# USB-TTL.net
KiCad netlist of a schematic drawn in EasyEDA Pro
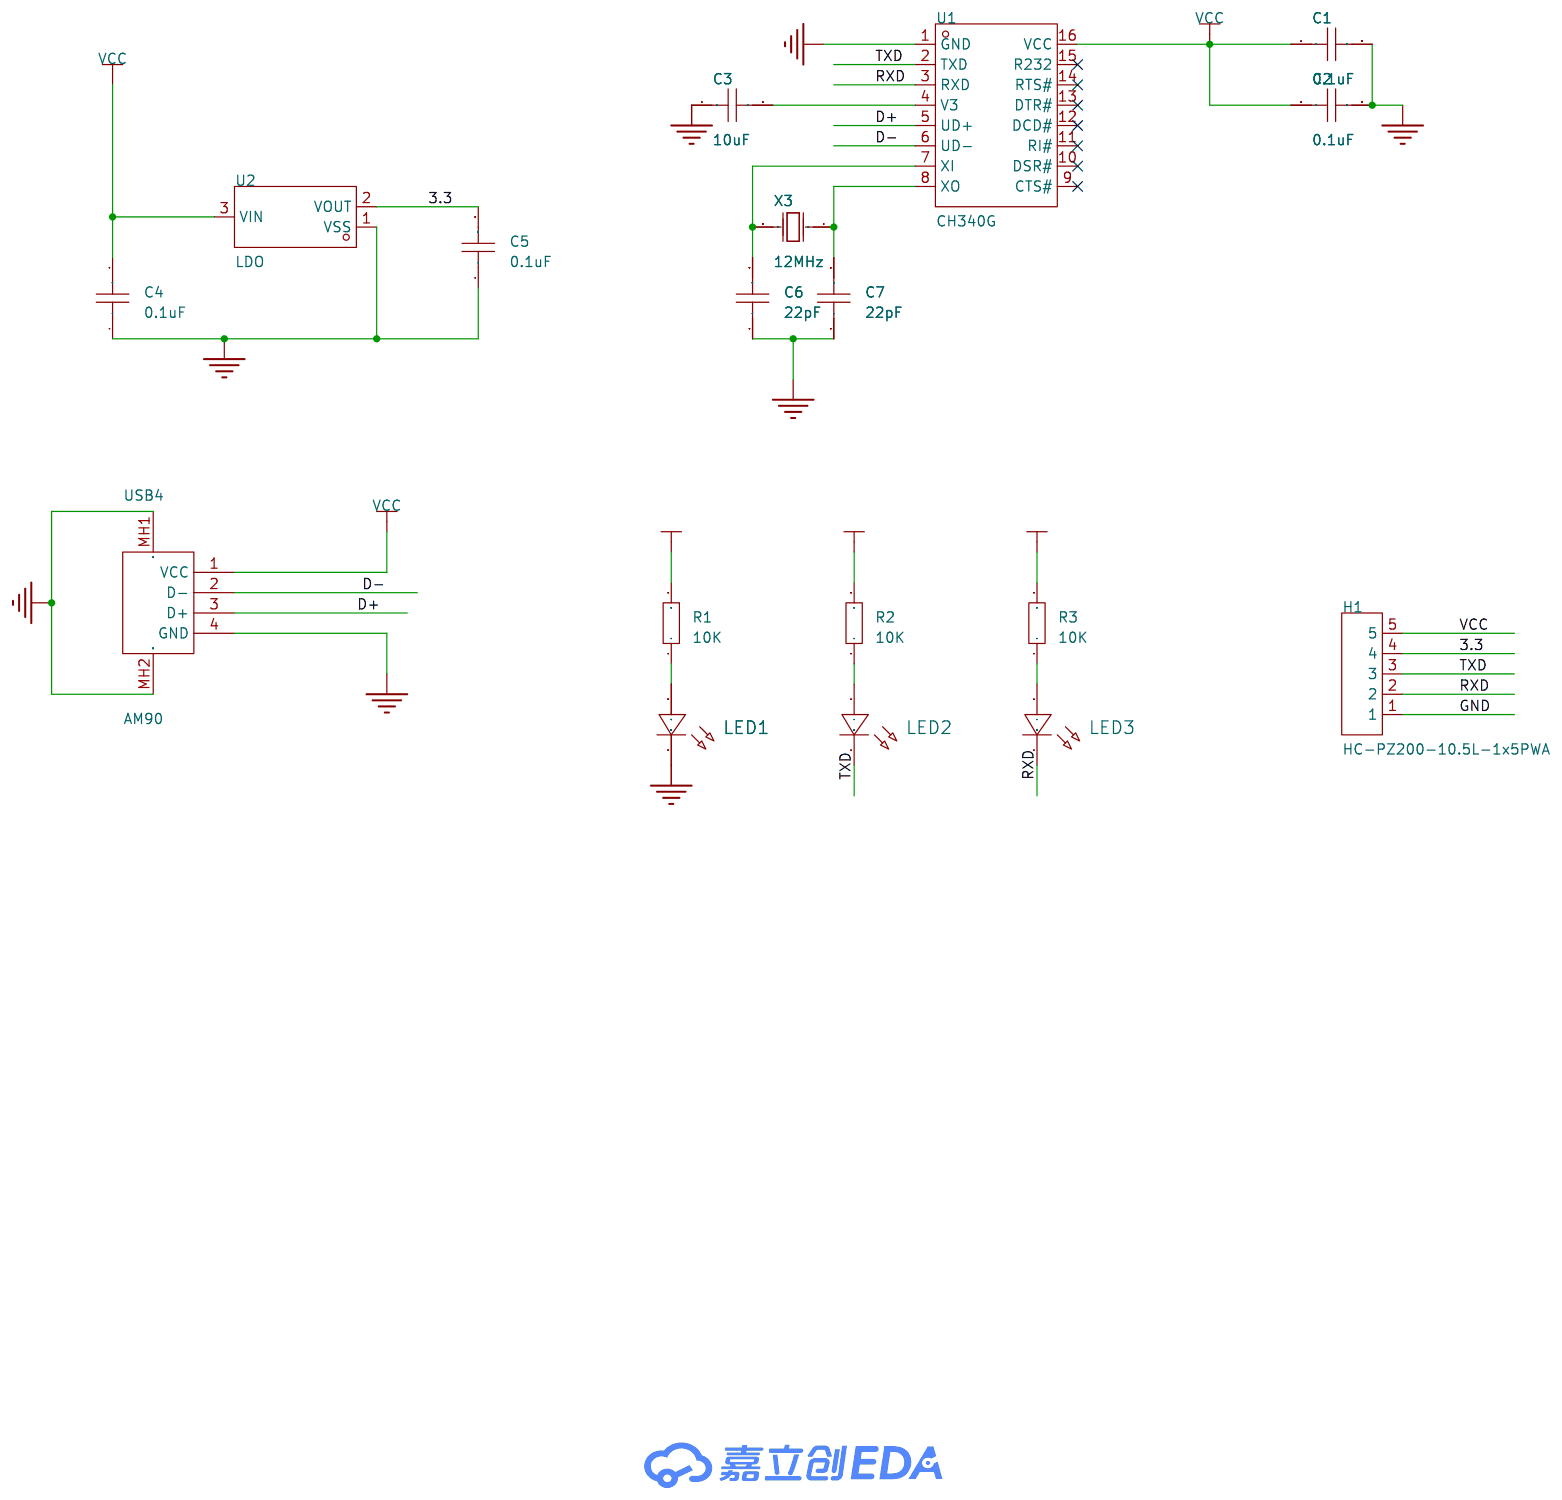
[diagram p0: schematic sheet]

(export (version "E")
  (design (tool "Eeschema 10.0.6"))
  (components
    (comp (ref "C1")
      (value "0.1uF")
      (footprint "easyedapro:C0603")
      (libsource (lib "easyedapro") (part "Capacitance"))
    )
    (comp (ref "C2")
      (value "0.1uF")
      (footprint "easyedapro:C0603")
      (libsource (lib "easyedapro") (part "Capacitance"))
    )
    (comp (ref "C3")
      (value "10uF")
      (footprint "easyedapro:C0603")
      (libsource (lib "easyedapro") (part "Capacitance"))
    )
    (comp (ref "C4")
      (value "0.1uF")
      (footprint "easyedapro:C0603")
      (libsource (lib "easyedapro") (part "Capacitance"))
    )
    (comp (ref "C5")
      (value "0.1uF")
      (footprint "easyedapro:C0603")
      (libsource (lib "easyedapro") (part "Capacitance"))
    )
    (comp (ref "C6")
      (value "22pF")
      (footprint "easyedapro:C0603")
      (libsource (lib "easyedapro") (part "Capacitance"))
    )
    (comp (ref "C7")
      (value "22pF")
      (footprint "easyedapro:C0603")
      (libsource (lib "easyedapro") (part "Capacitance"))
    )
    (comp (ref "H1")
      (value "HC-PZ200-10.5L-1x5PWA")
      (footprint "easyedapro:HDR-TH_5P-P2.00-H-M_2005WR-5P")
      (fields (field (name "Manufacturer") "HC(虹成电子)"))
      (libsource (lib "easyedapro") (part "HC-PZ200-10.5L-1X5PWA"))
    )
    (comp (ref "LED1")
      (value "~")
      (footprint "easyedapro:LED_0603")
      (libsource (lib "easyedapro") (part "LED_R"))
    )
    (comp (ref "LED2")
      (value "~")
      (footprint "easyedapro:LED_0603")
      (libsource (lib "easyedapro") (part "LED_R"))
    )
    (comp (ref "LED3")
      (value "~")
      (footprint "easyedapro:LED_0603")
      (libsource (lib "easyedapro") (part "LED_R"))
    )
    (comp (ref "R1") (value "10K") (footprint "easyedapro:R0603") (libsource (lib "easyedapro") (part "电阻")))
    (comp (ref "R2") (value "10K") (footprint "easyedapro:R0603") (libsource (lib "easyedapro") (part "电阻")))
    (comp (ref "R3") (value "10K") (footprint "easyedapro:R0603") (libsource (lib "easyedapro") (part "电阻")))
    (comp (ref "U1")
      (value "CH340G")
      (footprint "easyedapro:SOIC-16_L9.9-W3.9-P1.27-LS6.0-BL")
      (description "应用功能:USB转UART;接口协议:USB 2.0;数据速率:2Mbps;")
      (fields (field (name "Manufacturer") "WCH(南京沁恒)"))
      (libsource (lib "easyedapro") (part "CH340G"))
    )
    (comp (ref "U2")
      (value "LDO")
      (footprint "easyedapro:SOT-23-3_L3.0-W1.7-P0.95-LS2.9-BR")
      (description "输出类型:固定;工作电压:8V;输出电压:3.3V;输出电流:250mA;电源纹波抑制比(PSRR):40dB@(1kHz);输出极性:正极;")
      (fields (field (name "Manufacturer Part") "XC6206P332MR") (field (name "Manufacturer") "UMW(友台半导体)"))
      (libsource (lib "easyedapro") (part "XC6206P332MR_C347376"))
    )
    (comp (ref "USB4")
      (value "AM90")
      (footprint "easyedapro:USB-AM-TH_AM90")
      (description "连接器类型:Type-A;标准:USB 2.0;公母:公;安装方式:弯插;触点数量:4P;端口数量:1;额定电流 - 电源:1.5A;工作温度范围:-25°C~+85°C;")
      (fields (field (name "Manufacturer") "SHOU HAN(首韩)"))
      (libsource (lib "easyedapro") (part "AM90"))
    )
    (comp (ref "X3")
      (value "12MHz")
      (footprint "easyedapro:HC-49S_L11.4-W4.8")
      (description "晶振类型:贴片晶振;频率:12MHz;常温频差:±20ppm;负载电容:20pF;频率稳定度:±30ppm;")
      (fields (field (name "Manufacturer Part") "X49SM12MSD2SC") (field (name "Manufacturer") "YXC(扬兴晶振)"))
      (libsource (lib "easyedapro") (part "X49SM12MSD2SC"))
    )
  )
  (nets
    (net (code "1") (name "/D+") (class "Default")
      (node (ref "U1") (pin "5") (pinfunction "UD+_5") (pintype "unspecified"))
      (node (ref "USB4") (pin "3") (pinfunction "D+_3") (pintype "input"))
    )
    (net (code "2") (name "/D-") (class "Default")
      (node (ref "U1") (pin "6") (pinfunction "UD-_6") (pintype "unspecified"))
      (node (ref "USB4") (pin "2") (pinfunction "D-_2") (pintype "input"))
    )
    (net (code "3") (name "/RXD") (class "Default")
      (node (ref "H1") (pin "2") (pinfunction "2_2") (pintype "unspecified"))
      (node (ref "LED3") (pin "1") (pinfunction "C_1") (pintype "input"))
      (node (ref "U1") (pin "3") (pinfunction "RXD_3") (pintype "unspecified"))
    )
    (net (code "4") (name "/TXD") (class "Default")
      (node (ref "H1") (pin "3") (pinfunction "3_3") (pintype "unspecified"))
      (node (ref "LED2") (pin "1") (pinfunction "C_1") (pintype "input"))
      (node (ref "U1") (pin "2") (pinfunction "TXD_2") (pintype "unspecified"))
    )
    (net (code "5") (name "3.3") (class "Default")
      (node (ref "C5") (pin "2") (pinfunction "2_2") (pintype "input"))
      (node (ref "H1") (pin "4") (pinfunction "4_4") (pintype "unspecified"))
      (node (ref "R1") (pin "2") (pinfunction "2_2") (pintype "input"))
      (node (ref "R2") (pin "2") (pinfunction "2_2") (pintype "input"))
      (node (ref "R3") (pin "2") (pinfunction "2_2") (pintype "input"))
      (node (ref "U2") (pin "2") (pinfunction "VOUT_2") (pintype "unspecified"))
    )
    (net (code "6") (name "GND") (class "Default")
      (node (ref "C1") (pin "2") (pinfunction "2_2") (pintype "input"))
      (node (ref "C2") (pin "2") (pinfunction "2_2") (pintype "input"))
      (node (ref "C3") (pin "1") (pinfunction "1_1") (pintype "input"))
      (node (ref "C4") (pin "1") (pinfunction "1_1") (pintype "input"))
      (node (ref "C5") (pin "1") (pinfunction "1_1") (pintype "input"))
      (node (ref "C6") (pin "1") (pinfunction "1_1") (pintype "input"))
      (node (ref "C7") (pin "1") (pinfunction "1_1") (pintype "input"))
      (node (ref "H1") (pin "1") (pinfunction "1_1") (pintype "unspecified"))
      (node (ref "LED1") (pin "1") (pinfunction "C_1") (pintype "input"))
      (node (ref "U1") (pin "1") (pinfunction "GND_1") (pintype "unspecified"))
      (node (ref "U2") (pin "1") (pinfunction "VSS_1") (pintype "unspecified"))
      (node (ref "USB4") (pin "4") (pinfunction "GND_4") (pintype "input"))
      (node (ref "USB4") (pin "MH1") (pinfunction "MH1_MH1") (pintype "unspecified"))
      (node (ref "USB4") (pin "MH2") (pinfunction "MH2_MH2") (pintype "unspecified"))
    )
    (net (code "7") (name "Net-(LED1-A)") (class "Default")
      (node (ref "LED1") (pin "2") (pinfunction "A_2") (pintype "input"))
      (node (ref "R1") (pin "1") (pinfunction "1_1") (pintype "input"))
    )
    (net (code "8") (name "Net-(LED2-A)") (class "Default")
      (node (ref "LED2") (pin "2") (pinfunction "A_2") (pintype "input"))
      (node (ref "R2") (pin "1") (pinfunction "1_1") (pintype "input"))
    )
    (net (code "9") (name "Net-(LED3-A)") (class "Default")
      (node (ref "LED3") (pin "2") (pinfunction "A_2") (pintype "input"))
      (node (ref "R3") (pin "1") (pinfunction "1_1") (pintype "input"))
    )
    (net (code "10") (name "Net-(U1-V3)") (class "Default")
      (node (ref "C3") (pin "2") (pinfunction "2_2") (pintype "input"))
      (node (ref "U1") (pin "4") (pinfunction "V3_4") (pintype "unspecified"))
    )
    (net (code "11") (name "Net-(U1-XI)") (class "Default")
      (node (ref "C6") (pin "2") (pinfunction "2_2") (pintype "input"))
      (node (ref "U1") (pin "7") (pinfunction "XI_7") (pintype "unspecified"))
      (node (ref "X3") (pin "2") (pinfunction "OSC2_2") (pintype "input"))
    )
    (net (code "12") (name "Net-(U1-XO)") (class "Default")
      (node (ref "C7") (pin "2") (pinfunction "2_2") (pintype "input"))
      (node (ref "U1") (pin "8") (pinfunction "XO_8") (pintype "unspecified"))
      (node (ref "X3") (pin "1") (pinfunction "OSC1_1") (pintype "input"))
    )
    (net (code "13") (name "VCC") (class "Default")
      (node (ref "C1") (pin "1") (pinfunction "1_1") (pintype "input"))
      (node (ref "C2") (pin "1") (pinfunction "1_1") (pintype "input"))
      (node (ref "C4") (pin "2") (pinfunction "2_2") (pintype "input"))
      (node (ref "H1") (pin "5") (pinfunction "5_5") (pintype "unspecified"))
      (node (ref "U1") (pin "16") (pinfunction "VCC_16") (pintype "unspecified"))
      (node (ref "U2") (pin "3") (pinfunction "VIN_3") (pintype "unspecified"))
      (node (ref "USB4") (pin "1") (pinfunction "VCC_1") (pintype "input"))
    )
    (net (code "14") (name "unconnected-(U1-CTS#-Pad9)") (class "Default")
      (node (ref "U1") (pin "9") (pinfunction "CTS#_9") (pintype "unspecified+no_connect"))
    )
    (net (code "15") (name "unconnected-(U1-DCD#-Pad12)") (class "Default")
      (node (ref "U1") (pin "12") (pinfunction "DCD#_12") (pintype "unspecified+no_connect"))
    )
    (net (code "16") (name "unconnected-(U1-DSR#-Pad10)") (class "Default")
      (node (ref "U1") (pin "10") (pinfunction "DSR#_10") (pintype "unspecified+no_connect"))
    )
    (net (code "17") (name "unconnected-(U1-DTR#-Pad13)") (class "Default")
      (node (ref "U1") (pin "13") (pinfunction "DTR#_13") (pintype "unspecified+no_connect"))
    )
    (net (code "18") (name "unconnected-(U1-R232-Pad15)") (class "Default")
      (node (ref "U1") (pin "15") (pinfunction "R232_15") (pintype "unspecified+no_connect"))
    )
    (net (code "19") (name "unconnected-(U1-RI#-Pad11)") (class "Default")
      (node (ref "U1") (pin "11") (pinfunction "RI#_11") (pintype "unspecified+no_connect"))
    )
    (net (code "20") (name "unconnected-(U1-RTS#-Pad14)") (class "Default")
      (node (ref "U1") (pin "14") (pinfunction "RTS#_14") (pintype "unspecified+no_connect"))
    )
  )
)
